# 02_LEDs.net
KiCad netlist of a schematic drawn in Altium Designer
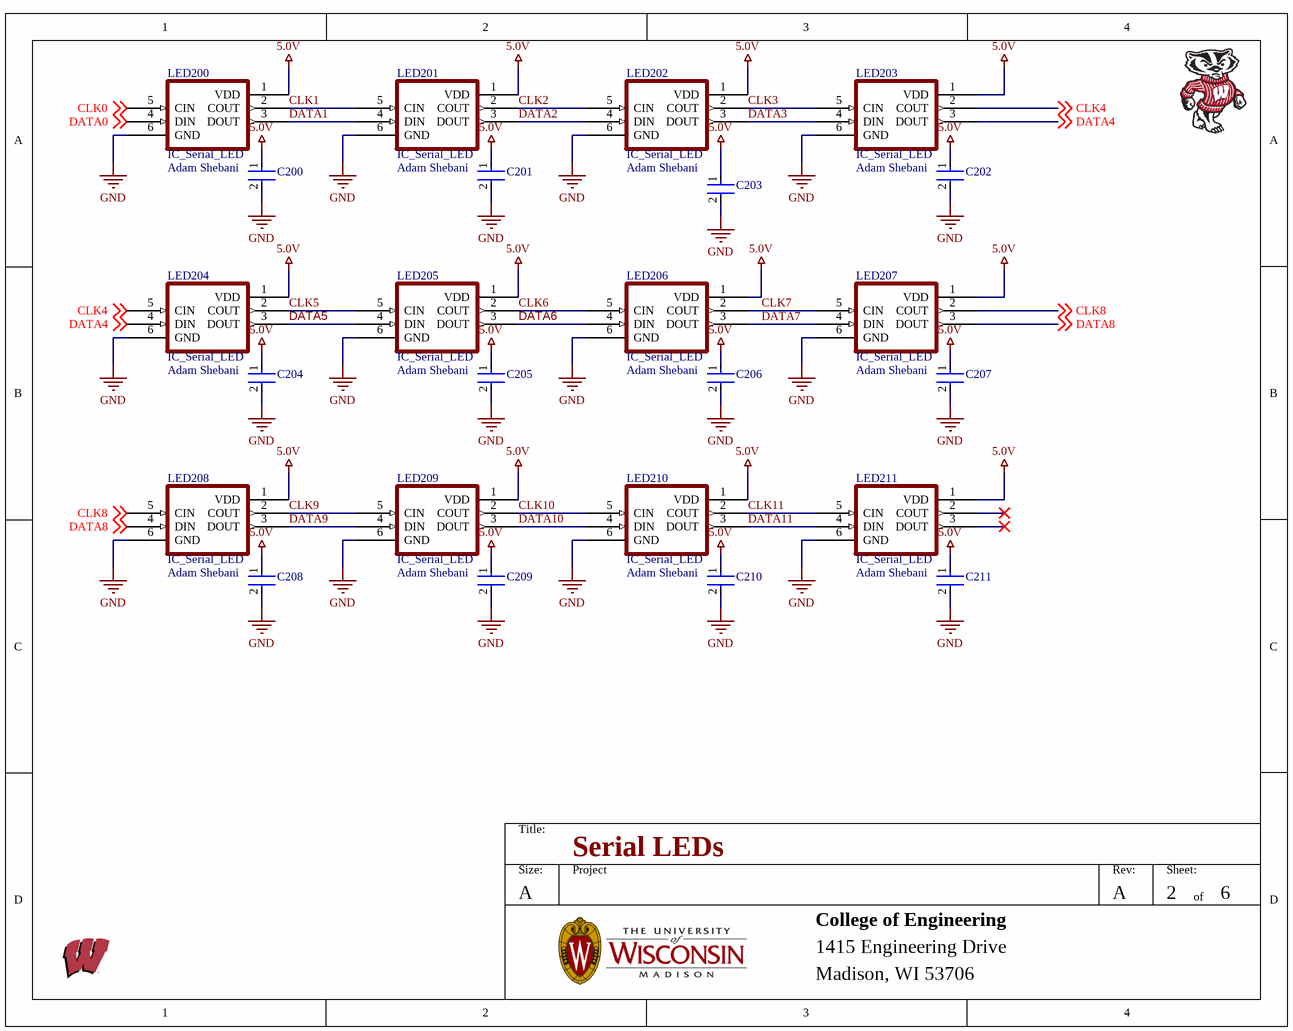
[diagram p0: 02_LEDs.SchDoc]

(export (version "E")
  (design (tool "Eeschema 10.0.6"))
  (components
    (comp (ref "C200")
      (value "CC1206KRX7R8BB104")
      (footprint "FP-CC1206-1_25-MFG")
      (description "CAP CER 0.1UF 25V X7R 1206")
      (fields
        (field (name "TOLERANCE") "0.1")
        (field (name "OCTOPART") "https://octopart.com/cc1206krx7r8bb104-yageo-42334534")
      )
      (libsource (lib "Altium Content Vault") (part "11868f565c42a9108669ba33697ecf6"))
    )
    (comp (ref "C201")
      (value "CC1206KRX7R8BB104")
      (footprint "FP-CC1206-1_25-MFG")
      (description "CAP CER 0.1UF 25V X7R 1206")
      (fields
        (field (name "TOLERANCE") "0.1")
        (field (name "OCTOPART") "https://octopart.com/cc1206krx7r8bb104-yageo-42334534")
      )
      (libsource (lib "Altium Content Vault") (part "11868f565c42a9108669ba33697ecf6"))
    )
    (comp (ref "C202")
      (value "CC1206KRX7R8BB104")
      (footprint "FP-CC1206-1_25-MFG")
      (description "CAP CER 0.1UF 25V X7R 1206")
      (fields
        (field (name "TOLERANCE") "0.1")
        (field (name "OCTOPART") "https://octopart.com/cc1206krx7r8bb104-yageo-42334534")
      )
      (libsource (lib "Altium Content Vault") (part "11868f565c42a9108669ba33697ecf6"))
    )
    (comp (ref "C203")
      (value "CC1206KRX7R8BB104")
      (footprint "FP-CC1206-1_25-MFG")
      (description "CAP CER 0.1UF 25V X7R 1206")
      (fields
        (field (name "TOLERANCE") "0.1")
        (field (name "OCTOPART") "https://octopart.com/cc1206krx7r8bb104-yageo-42334534")
      )
      (libsource (lib "Altium Content Vault") (part "11868f565c42a9108669ba33697ecf6"))
    )
    (comp (ref "C204")
      (value "CC1206KRX7R8BB104")
      (footprint "FP-CC1206-1_25-MFG")
      (description "CAP CER 0.1UF 25V X7R 1206")
      (fields
        (field (name "TOLERANCE") "0.1")
        (field (name "OCTOPART") "https://octopart.com/cc1206krx7r8bb104-yageo-42334534")
      )
      (libsource (lib "Altium Content Vault") (part "11868f565c42a9108669ba33697ecf6"))
    )
    (comp (ref "C205")
      (value "CC1206KRX7R8BB104")
      (footprint "FP-CC1206-1_25-MFG")
      (description "CAP CER 0.1UF 25V X7R 1206")
      (fields
        (field (name "TOLERANCE") "0.1")
        (field (name "OCTOPART") "https://octopart.com/cc1206krx7r8bb104-yageo-42334534")
      )
      (libsource (lib "Altium Content Vault") (part "11868f565c42a9108669ba33697ecf6"))
    )
    (comp (ref "C206")
      (value "CC1206KRX7R8BB104")
      (footprint "FP-CC1206-1_25-MFG")
      (description "CAP CER 0.1UF 25V X7R 1206")
      (fields
        (field (name "TOLERANCE") "0.1")
        (field (name "OCTOPART") "https://octopart.com/cc1206krx7r8bb104-yageo-42334534")
      )
      (libsource (lib "Altium Content Vault") (part "11868f565c42a9108669ba33697ecf6"))
    )
    (comp (ref "C207")
      (value "CC1206KRX7R8BB104")
      (footprint "FP-CC1206-1_25-MFG")
      (description "CAP CER 0.1UF 25V X7R 1206")
      (fields
        (field (name "TOLERANCE") "0.1")
        (field (name "OCTOPART") "https://octopart.com/cc1206krx7r8bb104-yageo-42334534")
      )
      (libsource (lib "Altium Content Vault") (part "11868f565c42a9108669ba33697ecf6"))
    )
    (comp (ref "C208")
      (value "CC1206KRX7R8BB104")
      (footprint "FP-CC1206-1_25-MFG")
      (description "CAP CER 0.1UF 25V X7R 1206")
      (fields
        (field (name "TOLERANCE") "0.1")
        (field (name "OCTOPART") "https://octopart.com/cc1206krx7r8bb104-yageo-42334534")
      )
      (libsource (lib "Altium Content Vault") (part "11868f565c42a9108669ba33697ecf6"))
    )
    (comp (ref "C209")
      (value "CC1206KRX7R8BB104")
      (footprint "FP-CC1206-1_25-MFG")
      (description "CAP CER 0.1UF 25V X7R 1206")
      (fields
        (field (name "TOLERANCE") "0.1")
        (field (name "OCTOPART") "https://octopart.com/cc1206krx7r8bb104-yageo-42334534")
      )
      (libsource (lib "Altium Content Vault") (part "11868f565c42a9108669ba33697ecf6"))
    )
    (comp (ref "C210")
      (value "CC1206KRX7R8BB104")
      (footprint "FP-CC1206-1_25-MFG")
      (description "CAP CER 0.1UF 25V X7R 1206")
      (fields
        (field (name "TOLERANCE") "0.1")
        (field (name "OCTOPART") "https://octopart.com/cc1206krx7r8bb104-yageo-42334534")
      )
      (libsource (lib "Altium Content Vault") (part "11868f565c42a9108669ba33697ecf6"))
    )
    (comp (ref "C211")
      (value "CC1206KRX7R8BB104")
      (footprint "FP-CC1206-1_25-MFG")
      (description "CAP CER 0.1UF 25V X7R 1206")
      (fields
        (field (name "TOLERANCE") "0.1")
        (field (name "OCTOPART") "https://octopart.com/cc1206krx7r8bb104-yageo-42334534")
      )
      (libsource (lib "Altium Content Vault") (part "11868f565c42a9108669ba33697ecf6"))
    )
    (comp (ref "LED200")
      (value "IC_Serial_LED")
      (footprint "IC_Serial_LED")
      (fields
        (field (name "MANUFACTURER") "Harvatek")
        (field (name "MANUFACTURER PART NUMBER") "T3A33BRG-H9C0002X1U1930")
        (field (name "DRAWN BY") "Adam Shebani")
      )
      (libsource (lib "ECE315-F25") (part "IC_Serial_LED"))
    )
    (comp (ref "LED201")
      (value "IC_Serial_LED")
      (footprint "IC_Serial_LED")
      (fields
        (field (name "MANUFACTURER") "Harvatek")
        (field (name "MANUFACTURER PART NUMBER") "T3A33BRG-H9C0002X1U1930")
        (field (name "DRAWN BY") "Adam Shebani")
      )
      (libsource (lib "ECE315-F25") (part "IC_Serial_LED"))
    )
    (comp (ref "LED202")
      (value "IC_Serial_LED")
      (footprint "IC_Serial_LED")
      (fields
        (field (name "MANUFACTURER") "Harvatek")
        (field (name "MANUFACTURER PART NUMBER") "T3A33BRG-H9C0002X1U1930")
        (field (name "DRAWN BY") "Adam Shebani")
      )
      (libsource (lib "ECE315-F25") (part "IC_Serial_LED"))
    )
    (comp (ref "LED203")
      (value "IC_Serial_LED")
      (footprint "IC_Serial_LED")
      (fields
        (field (name "MANUFACTURER") "Harvatek")
        (field (name "MANUFACTURER PART NUMBER") "T3A33BRG-H9C0002X1U1930")
        (field (name "DRAWN BY") "Adam Shebani")
      )
      (libsource (lib "ECE315-F25") (part "IC_Serial_LED"))
    )
    (comp (ref "LED204")
      (value "IC_Serial_LED")
      (footprint "IC_Serial_LED")
      (fields
        (field (name "MANUFACTURER") "Harvatek")
        (field (name "MANUFACTURER PART NUMBER") "T3A33BRG-H9C0002X1U1930")
        (field (name "DRAWN BY") "Adam Shebani")
      )
      (libsource (lib "ECE315-F25") (part "IC_Serial_LED"))
    )
    (comp (ref "LED205")
      (value "IC_Serial_LED")
      (footprint "IC_Serial_LED")
      (fields
        (field (name "MANUFACTURER") "Harvatek")
        (field (name "MANUFACTURER PART NUMBER") "T3A33BRG-H9C0002X1U1930")
        (field (name "DRAWN BY") "Adam Shebani")
      )
      (libsource (lib "ECE315-F25") (part "IC_Serial_LED"))
    )
    (comp (ref "LED206")
      (value "IC_Serial_LED")
      (footprint "IC_Serial_LED")
      (fields
        (field (name "MANUFACTURER") "Harvatek")
        (field (name "MANUFACTURER PART NUMBER") "T3A33BRG-H9C0002X1U1930")
        (field (name "DRAWN BY") "Adam Shebani")
      )
      (libsource (lib "ECE315-F25") (part "IC_Serial_LED"))
    )
    (comp (ref "LED207")
      (value "IC_Serial_LED")
      (footprint "IC_Serial_LED")
      (fields
        (field (name "MANUFACTURER") "Harvatek")
        (field (name "MANUFACTURER PART NUMBER") "T3A33BRG-H9C0002X1U1930")
        (field (name "DRAWN BY") "Adam Shebani")
      )
      (libsource (lib "ECE315-F25") (part "IC_Serial_LED"))
    )
    (comp (ref "LED208")
      (value "IC_Serial_LED")
      (footprint "IC_Serial_LED")
      (fields
        (field (name "MANUFACTURER") "Harvatek")
        (field (name "MANUFACTURER PART NUMBER") "T3A33BRG-H9C0002X1U1930")
        (field (name "DRAWN BY") "Adam Shebani")
      )
      (libsource (lib "ECE315-F25") (part "IC_Serial_LED"))
    )
    (comp (ref "LED209")
      (value "IC_Serial_LED")
      (footprint "IC_Serial_LED")
      (fields
        (field (name "MANUFACTURER") "Harvatek")
        (field (name "MANUFACTURER PART NUMBER") "T3A33BRG-H9C0002X1U1930")
        (field (name "DRAWN BY") "Adam Shebani")
      )
      (libsource (lib "ECE315-F25") (part "IC_Serial_LED"))
    )
    (comp (ref "LED210")
      (value "IC_Serial_LED")
      (footprint "IC_Serial_LED")
      (fields
        (field (name "MANUFACTURER") "Harvatek")
        (field (name "MANUFACTURER PART NUMBER") "T3A33BRG-H9C0002X1U1930")
        (field (name "DRAWN BY") "Adam Shebani")
      )
      (libsource (lib "ECE315-F25") (part "IC_Serial_LED"))
    )
    (comp (ref "LED211")
      (value "IC_Serial_LED")
      (footprint "IC_Serial_LED")
      (fields
        (field (name "MANUFACTURER") "Harvatek")
        (field (name "MANUFACTURER PART NUMBER") "T3A33BRG-H9C0002X1U1930")
        (field (name "DRAWN BY") "Adam Shebani")
      )
      (libsource (lib "ECE315-F25") (part "IC_Serial_LED"))
    )
  )
  (nets
    (net (code "1") (name "/CLK1") (class "Default")
      (node (ref "LED200") (pin "2") (pinfunction "COUT_2") (pintype "output"))
      (node (ref "LED201") (pin "5") (pinfunction "CIN_5") (pintype "input"))
    )
    (net (code "2") (name "/CLK2") (class "Default")
      (node (ref "LED201") (pin "2") (pinfunction "COUT_2") (pintype "output"))
      (node (ref "LED202") (pin "5") (pinfunction "CIN_5") (pintype "input"))
    )
    (net (code "3") (name "/CLK3") (class "Default")
      (node (ref "LED202") (pin "2") (pinfunction "COUT_2") (pintype "output"))
      (node (ref "LED203") (pin "5") (pinfunction "CIN_5") (pintype "input"))
    )
    (net (code "4") (name "/CLK5") (class "Default")
      (node (ref "LED204") (pin "2") (pinfunction "COUT_2") (pintype "output"))
      (node (ref "LED205") (pin "5") (pinfunction "CIN_5") (pintype "input"))
    )
    (net (code "5") (name "/CLK6") (class "Default")
      (node (ref "LED205") (pin "2") (pinfunction "COUT_2") (pintype "output"))
      (node (ref "LED206") (pin "5") (pinfunction "CIN_5") (pintype "input"))
    )
    (net (code "6") (name "/CLK7") (class "Default")
      (node (ref "LED206") (pin "2") (pinfunction "COUT_2") (pintype "output"))
      (node (ref "LED207") (pin "5") (pinfunction "CIN_5") (pintype "input"))
    )
    (net (code "7") (name "/CLK9") (class "Default")
      (node (ref "LED208") (pin "2") (pinfunction "COUT_2") (pintype "output"))
      (node (ref "LED209") (pin "5") (pinfunction "CIN_5") (pintype "input"))
    )
    (net (code "8") (name "/CLK10") (class "Default")
      (node (ref "LED209") (pin "2") (pinfunction "COUT_2") (pintype "output"))
      (node (ref "LED210") (pin "5") (pinfunction "CIN_5") (pintype "input"))
    )
    (net (code "9") (name "/CLK11") (class "Default")
      (node (ref "LED210") (pin "2") (pinfunction "COUT_2") (pintype "output"))
      (node (ref "LED211") (pin "5") (pinfunction "CIN_5") (pintype "input"))
    )
    (net (code "10") (name "/DATA1") (class "Default")
      (node (ref "LED200") (pin "3") (pinfunction "DOUT_3") (pintype "output"))
      (node (ref "LED201") (pin "4") (pinfunction "DIN_4") (pintype "input"))
    )
    (net (code "11") (name "/DATA2") (class "Default")
      (node (ref "LED201") (pin "3") (pinfunction "DOUT_3") (pintype "output"))
      (node (ref "LED202") (pin "4") (pinfunction "DIN_4") (pintype "input"))
    )
    (net (code "12") (name "/DATA3") (class "Default")
      (node (ref "LED202") (pin "3") (pinfunction "DOUT_3") (pintype "output"))
      (node (ref "LED203") (pin "4") (pinfunction "DIN_4") (pintype "input"))
    )
    (net (code "13") (name "/DATA5") (class "Default")
      (node (ref "LED204") (pin "3") (pinfunction "DOUT_3") (pintype "output"))
      (node (ref "LED205") (pin "4") (pinfunction "DIN_4") (pintype "input"))
    )
    (net (code "14") (name "/DATA6") (class "Default")
      (node (ref "LED205") (pin "3") (pinfunction "DOUT_3") (pintype "output"))
      (node (ref "LED206") (pin "4") (pinfunction "DIN_4") (pintype "input"))
    )
    (net (code "15") (name "/DATA7") (class "Default")
      (node (ref "LED206") (pin "3") (pinfunction "DOUT_3") (pintype "output"))
      (node (ref "LED207") (pin "4") (pinfunction "DIN_4") (pintype "input"))
    )
    (net (code "16") (name "/DATA9") (class "Default")
      (node (ref "LED208") (pin "3") (pinfunction "DOUT_3") (pintype "output"))
      (node (ref "LED209") (pin "4") (pinfunction "DIN_4") (pintype "input"))
    )
    (net (code "17") (name "/DATA10") (class "Default")
      (node (ref "LED209") (pin "3") (pinfunction "DOUT_3") (pintype "output"))
      (node (ref "LED210") (pin "4") (pinfunction "DIN_4") (pintype "input"))
    )
    (net (code "18") (name "/DATA11") (class "Default")
      (node (ref "LED210") (pin "3") (pinfunction "DOUT_3") (pintype "output"))
      (node (ref "LED211") (pin "4") (pinfunction "DIN_4") (pintype "input"))
    )
    (net (code "19") (name "5.0V") (class "Default")
      (node (ref "C200") (pin "1") (pinfunction "1_1") (pintype "passive"))
      (node (ref "C201") (pin "1") (pinfunction "1_1") (pintype "passive"))
      (node (ref "C202") (pin "1") (pinfunction "1_1") (pintype "passive"))
      (node (ref "C203") (pin "1") (pinfunction "1_1") (pintype "passive"))
      (node (ref "C204") (pin "1") (pinfunction "1_1") (pintype "passive"))
      (node (ref "C205") (pin "1") (pinfunction "1_1") (pintype "passive"))
      (node (ref "C206") (pin "1") (pinfunction "1_1") (pintype "passive"))
      (node (ref "C207") (pin "1") (pinfunction "1_1") (pintype "passive"))
      (node (ref "C208") (pin "1") (pinfunction "1_1") (pintype "passive"))
      (node (ref "C209") (pin "1") (pinfunction "1_1") (pintype "passive"))
      (node (ref "C210") (pin "1") (pinfunction "1_1") (pintype "passive"))
      (node (ref "C211") (pin "1") (pinfunction "1_1") (pintype "passive"))
      (node (ref "LED200") (pin "1") (pinfunction "VDD_1") (pintype "power_in"))
      (node (ref "LED201") (pin "1") (pinfunction "VDD_1") (pintype "power_in"))
      (node (ref "LED202") (pin "1") (pinfunction "VDD_1") (pintype "power_in"))
      (node (ref "LED203") (pin "1") (pinfunction "VDD_1") (pintype "power_in"))
      (node (ref "LED204") (pin "1") (pinfunction "VDD_1") (pintype "power_in"))
      (node (ref "LED205") (pin "1") (pinfunction "VDD_1") (pintype "power_in"))
      (node (ref "LED206") (pin "1") (pinfunction "VDD_1") (pintype "power_in"))
      (node (ref "LED207") (pin "1") (pinfunction "VDD_1") (pintype "power_in"))
      (node (ref "LED208") (pin "1") (pinfunction "VDD_1") (pintype "power_in"))
      (node (ref "LED209") (pin "1") (pinfunction "VDD_1") (pintype "power_in"))
      (node (ref "LED210") (pin "1") (pinfunction "VDD_1") (pintype "power_in"))
      (node (ref "LED211") (pin "1") (pinfunction "VDD_1") (pintype "power_in"))
    )
    (net (code "20") (name "CLK0") (class "Default")
      (node (ref "LED200") (pin "5") (pinfunction "CIN_5") (pintype "input"))
    )
    (net (code "21") (name "CLK4") (class "Default")
      (node (ref "LED203") (pin "2") (pinfunction "COUT_2") (pintype "output"))
      (node (ref "LED204") (pin "5") (pinfunction "CIN_5") (pintype "input"))
    )
    (net (code "22") (name "CLK8") (class "Default")
      (node (ref "LED207") (pin "2") (pinfunction "COUT_2") (pintype "output"))
      (node (ref "LED208") (pin "5") (pinfunction "CIN_5") (pintype "input"))
    )
    (net (code "23") (name "DATA0") (class "Default")
      (node (ref "LED200") (pin "4") (pinfunction "DIN_4") (pintype "input"))
    )
    (net (code "24") (name "DATA4") (class "Default")
      (node (ref "LED203") (pin "3") (pinfunction "DOUT_3") (pintype "output"))
      (node (ref "LED204") (pin "4") (pinfunction "DIN_4") (pintype "input"))
    )
    (net (code "25") (name "DATA8") (class "Default")
      (node (ref "LED207") (pin "3") (pinfunction "DOUT_3") (pintype "output"))
      (node (ref "LED208") (pin "4") (pinfunction "DIN_4") (pintype "input"))
    )
    (net (code "26") (name "GND") (class "Default")
      (node (ref "C200") (pin "2") (pinfunction "2_2") (pintype "passive"))
      (node (ref "C201") (pin "2") (pinfunction "2_2") (pintype "passive"))
      (node (ref "C202") (pin "2") (pinfunction "2_2") (pintype "passive"))
      (node (ref "C203") (pin "2") (pinfunction "2_2") (pintype "passive"))
      (node (ref "C204") (pin "2") (pinfunction "2_2") (pintype "passive"))
      (node (ref "C205") (pin "2") (pinfunction "2_2") (pintype "passive"))
      (node (ref "C206") (pin "2") (pinfunction "2_2") (pintype "passive"))
      (node (ref "C207") (pin "2") (pinfunction "2_2") (pintype "passive"))
      (node (ref "C208") (pin "2") (pinfunction "2_2") (pintype "passive"))
      (node (ref "C209") (pin "2") (pinfunction "2_2") (pintype "passive"))
      (node (ref "C210") (pin "2") (pinfunction "2_2") (pintype "passive"))
      (node (ref "C211") (pin "2") (pinfunction "2_2") (pintype "passive"))
      (node (ref "LED200") (pin "6") (pinfunction "GND_6") (pintype "power_in"))
      (node (ref "LED201") (pin "6") (pinfunction "GND_6") (pintype "power_in"))
      (node (ref "LED202") (pin "6") (pinfunction "GND_6") (pintype "power_in"))
      (node (ref "LED203") (pin "6") (pinfunction "GND_6") (pintype "power_in"))
      (node (ref "LED204") (pin "6") (pinfunction "GND_6") (pintype "power_in"))
      (node (ref "LED205") (pin "6") (pinfunction "GND_6") (pintype "power_in"))
      (node (ref "LED206") (pin "6") (pinfunction "GND_6") (pintype "power_in"))
      (node (ref "LED207") (pin "6") (pinfunction "GND_6") (pintype "power_in"))
      (node (ref "LED208") (pin "6") (pinfunction "GND_6") (pintype "power_in"))
      (node (ref "LED209") (pin "6") (pinfunction "GND_6") (pintype "power_in"))
      (node (ref "LED210") (pin "6") (pinfunction "GND_6") (pintype "power_in"))
      (node (ref "LED211") (pin "6") (pinfunction "GND_6") (pintype "power_in"))
    )
    (net (code "27") (name "unconnected-(LED211-COUT-Pad2)") (class "Default")
      (node (ref "LED211") (pin "2") (pinfunction "COUT_2") (pintype "output+no_connect"))
    )
    (net (code "28") (name "unconnected-(LED211-DOUT-Pad3)") (class "Default")
      (node (ref "LED211") (pin "3") (pinfunction "DOUT_3") (pintype "output+no_connect"))
    )
  )
)
